# 04_-_MAIN.net
KiCad netlist of a schematic drawn in Altium Designer
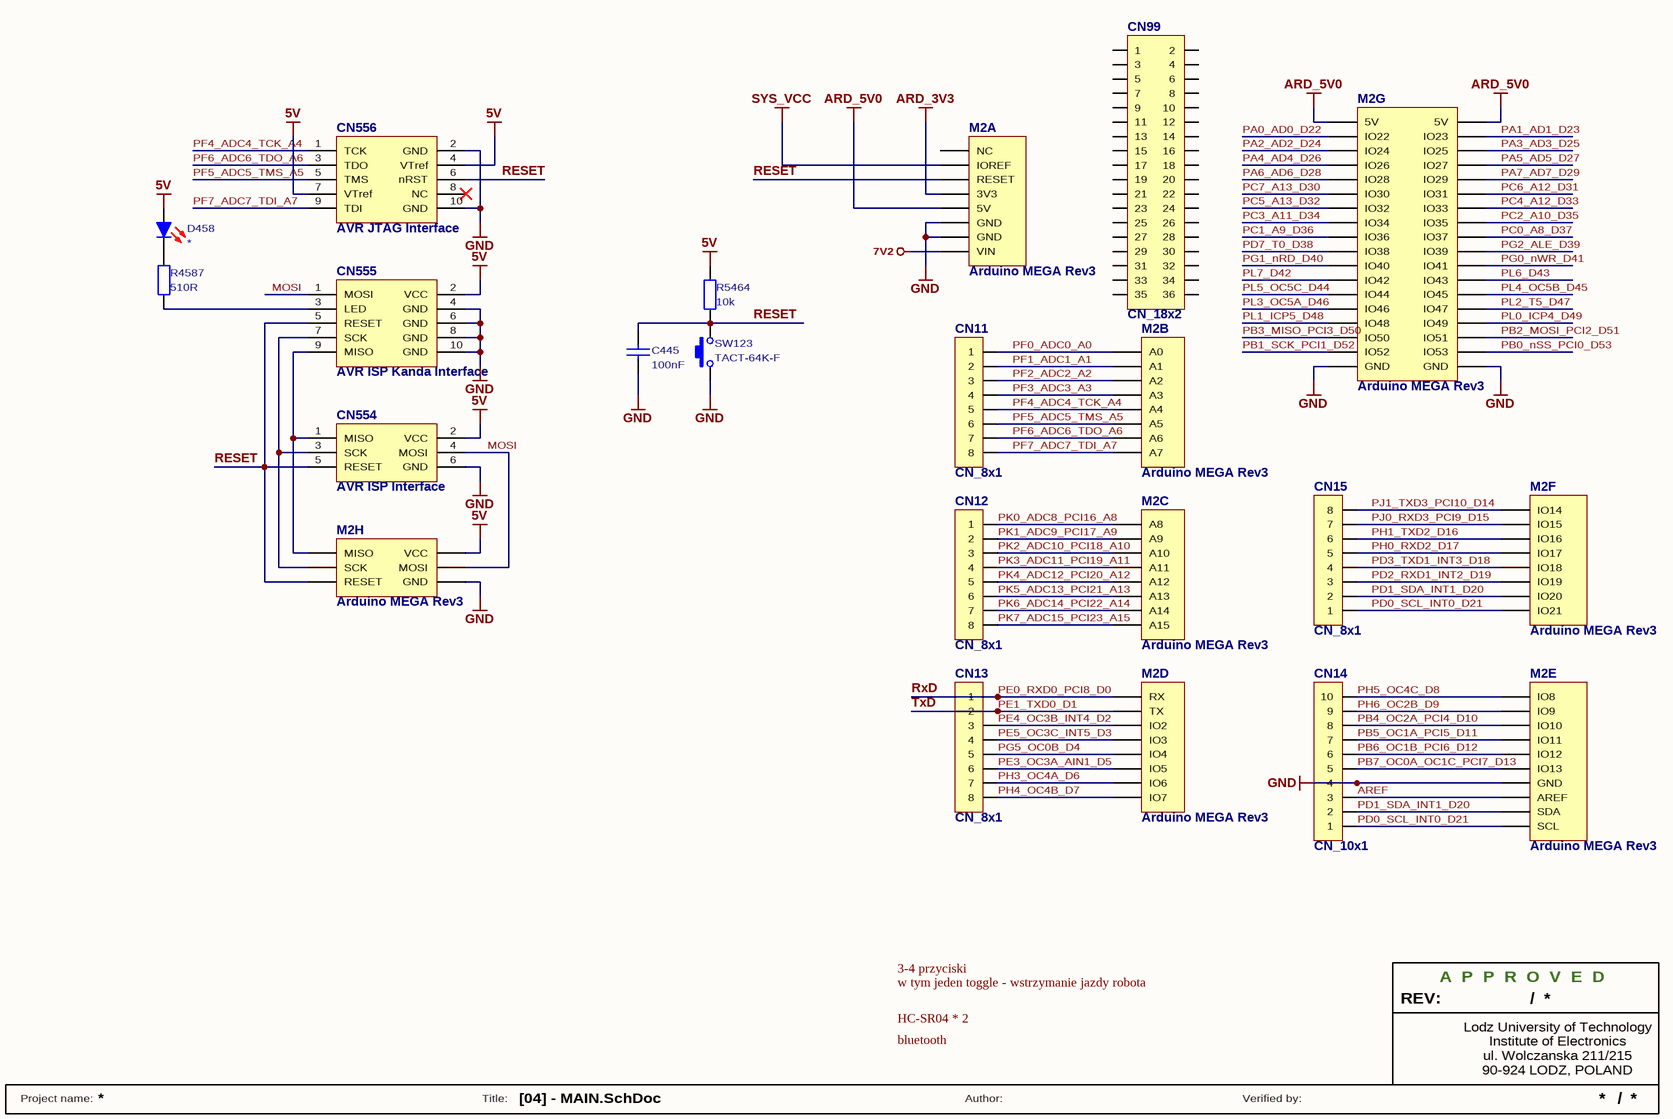
[diagram p0: [04] - MAIN.SchDoc]

(export (version "E")
  (design (tool "Eeschema 10.0.6"))
  (components
    (comp (ref "C445")
      (value "100nF")
      (footprint "C1206")
      (description "Capacitor")
      (libsource (lib "capacitors") (part "Cap"))
    )
    (comp (ref "CN11") (value "CN_8x1") (footprint "GP_8x1") (libsource (lib "") (part "CN_8x1_1")))
    (comp (ref "CN12") (value "CN_8x1") (footprint "GP_8x1") (libsource (lib "") (part "CN_8x1_1")))
    (comp (ref "CN13") (value "CN_8x1") (footprint "GP_8x1") (libsource (lib "") (part "CN_8x1_1")))
    (comp (ref "CN14")
      (value "CN_10x1")
      (footprint "GP_10x1")
      (libsource (lib "goldpin_male") (part "CN_10x1"))
    )
    (comp (ref "CN15") (value "CN_8x1") (footprint "GP_8x1") (libsource (lib "goldpin_male") (part "CN_8x1")))
    (comp (ref "CN99")
      (value "CN_18x2")
      (footprint "GP_18x2")
      (libsource (lib "goldpin_male") (part "CN_18x2"))
    )
    (comp (ref "CN554")
      (value "AVR ISP Interface")
      (footprint "IDC6")
      (description "ISP Programming Header for AVR MCU's")
      (libsource (lib "mcu_prog_and_debug_connectors") (part "AVR ISP Interface"))
    )
    (comp (ref "CN555")
      (value "AVR ISP Kanda Interface")
      (footprint "IDC10")
      (description "Kanda ISP Programming Header for AVR MCU's")
      (libsource (lib "mcu_prog_and_debug_connectors") (part "AVR ISP Kanda Interface"))
    )
    (comp (ref "CN556")
      (value "AVR JTAG Interface")
      (footprint "IDC10")
      (description "JTAG Header for AVR MCU's")
      (libsource (lib "mcu_prog_and_debug_connectors") (part "AVR JTAG Interface"))
    )
    (comp (ref "D458")
      (value "*")
      (footprint "LED1206R")
      (description "RED LED")
      (libsource (lib "leds") (part "LED_RED"))
    )
    (comp (ref "M2")
      (value "Arduino MEGA Rev3")
      (footprint "Arduino_MEGA_UPSIDE_DOWN")
      (description "Arduino MEGA Rev3 Board")
      (libsource (lib "mcu_modules") (part "Arduino MEGA Rev3"))
    )
    (comp (ref "R4587")
      (value "510R")
      (footprint "R1206")
      (description "Resistor")
      (libsource (lib "resistors") (part "Res"))
    )
    (comp (ref "R5464")
      (value "10k")
      (footprint "R1206")
      (description "Resistor")
      (libsource (lib "resistors") (part "Res"))
    )
    (comp (ref "SW123")
      (value "TACT-64K-F")
      (footprint "TACT-64K-F")
      (description "6x6mm THT Tactile SPST-NO Switch")
      (libsource (lib "microswitches") (part "TACT-64K-F"))
    )
  )
  (nets
    (net (code "2") (name "/AREF") (class "Default")
      (node (ref "CN14") (pin "3") (pinfunction "3_3") (pintype "passive"))
      (node (ref "M2") (pin "D15") (pinfunction "AREF_D15") (pintype "passive"))
    )
    (net (code "4") (name "/MOSI") (class "Default")
      (node (ref "CN554") (pin "4") (pinfunction "MOSI_4") (pintype "passive"))
      (node (ref "CN555") (pin "1") (pinfunction "MOSI_1") (pintype "passive"))
      (node (ref "M2") (pin "PROG4") (pinfunction "MOSI_PROG4") (pintype "passive"))
    )
    (net (code "5") (name "/PA0_AD0_D22") (class "Default")
      (node (ref "M2") (pin "D28") (pinfunction "IO22_D28") (pintype "passive"))
    )
    (net (code "6") (name "/PA1_AD1_D23") (class "Default")
      (node (ref "M2") (pin "D29") (pinfunction "IO23_D29") (pintype "passive"))
    )
    (net (code "7") (name "/PA2_AD2_D24") (class "Default")
      (node (ref "M2") (pin "D30") (pinfunction "IO24_D30") (pintype "passive"))
    )
    (net (code "8") (name "/PA3_AD3_D25") (class "Default")
      (node (ref "M2") (pin "D31") (pinfunction "IO25_D31") (pintype "passive"))
    )
    (net (code "9") (name "/PA4_AD4_D26") (class "Default")
      (node (ref "M2") (pin "D32") (pinfunction "IO26_D32") (pintype "passive"))
    )
    (net (code "10") (name "/PA5_AD5_D27") (class "Default")
      (node (ref "M2") (pin "D33") (pinfunction "IO27_D33") (pintype "passive"))
    )
    (net (code "11") (name "/PA6_AD6_D28") (class "Default")
      (node (ref "M2") (pin "D34") (pinfunction "IO28_D34") (pintype "passive"))
    )
    (net (code "12") (name "/PA7_AD7_D29") (class "Default")
      (node (ref "M2") (pin "D35") (pinfunction "IO29_D35") (pintype "passive"))
    )
    (net (code "13") (name "/PB0_nSS_PCI0_D53") (class "Default")
      (node (ref "M2") (pin "D59") (pinfunction "IO53_D59") (pintype "passive"))
    )
    (net (code "14") (name "/PB1_SCK_PCI1_D52") (class "Default")
      (node (ref "M2") (pin "D58") (pinfunction "IO52_D58") (pintype "passive"))
    )
    (net (code "15") (name "/PB2_MOSI_PCI2_D51") (class "Default")
      (node (ref "M2") (pin "D57") (pinfunction "IO51_D57") (pintype "passive"))
    )
    (net (code "16") (name "/PB3_MISO_PCI3_D50") (class "Default")
      (node (ref "M2") (pin "D56") (pinfunction "IO50_D56") (pintype "passive"))
    )
    (net (code "17") (name "/PB4_OC2A_PCI4_D10") (class "Default")
      (node (ref "CN14") (pin "8") (pinfunction "8_8") (pintype "passive"))
      (node (ref "M2") (pin "D10") (pinfunction "IO10_D10") (pintype "passive"))
    )
    (net (code "18") (name "/PB5_OC1A_PCI5_D11") (class "Default")
      (node (ref "CN14") (pin "7") (pinfunction "7_7") (pintype "passive"))
      (node (ref "M2") (pin "D11") (pinfunction "IO11_D11") (pintype "passive"))
    )
    (net (code "19") (name "/PB6_OC1B_PCI6_D12") (class "Default")
      (node (ref "CN14") (pin "6") (pinfunction "6_6") (pintype "passive"))
      (node (ref "M2") (pin "D12") (pinfunction "IO12_D12") (pintype "passive"))
    )
    (net (code "20") (name "/PB7_OC0A_OC1C_PCI7_D13") (class "Default")
      (node (ref "CN14") (pin "5") (pinfunction "5_5") (pintype "passive"))
      (node (ref "M2") (pin "D13") (pinfunction "IO13_D13") (pintype "passive"))
    )
    (net (code "21") (name "/PC0_A8_D37") (class "Default")
      (node (ref "M2") (pin "D43") (pinfunction "IO37_D43") (pintype "passive"))
    )
    (net (code "22") (name "/PC1_A9_D36") (class "Default")
      (node (ref "M2") (pin "D42") (pinfunction "IO36_D42") (pintype "passive"))
    )
    (net (code "23") (name "/PC2_A10_D35") (class "Default")
      (node (ref "M2") (pin "D41") (pinfunction "IO35_D41") (pintype "passive"))
    )
    (net (code "24") (name "/PC3_A11_D34") (class "Default")
      (node (ref "M2") (pin "D40") (pinfunction "IO34_D40") (pintype "passive"))
    )
    (net (code "25") (name "/PC4_A12_D33") (class "Default")
      (node (ref "M2") (pin "D39") (pinfunction "IO33_D39") (pintype "passive"))
    )
    (net (code "26") (name "/PC5_A13_D32") (class "Default")
      (node (ref "M2") (pin "D38") (pinfunction "IO32_D38") (pintype "passive"))
    )
    (net (code "27") (name "/PC6_A12_D31") (class "Default")
      (node (ref "M2") (pin "D37") (pinfunction "IO31_D37") (pintype "passive"))
    )
    (net (code "28") (name "/PC7_A13_D30") (class "Default")
      (node (ref "M2") (pin "D36") (pinfunction "IO30_D36") (pintype "passive"))
    )
    (net (code "29") (name "/PD0_SCL_INT0_D21") (class "Default")
      (node (ref "CN14") (pin "1") (pinfunction "1_1") (pintype "passive"))
      (node (ref "CN15") (pin "1") (pinfunction "1_1") (pintype "passive"))
      (node (ref "M2") (pin "D17") (pinfunction "SCL_D17") (pintype "passive"))
      (node (ref "M2") (pin "D25") (pinfunction "IO21_D25") (pintype "passive"))
    )
    (net (code "30") (name "/PD1_SDA_INT1_D20") (class "Default")
      (node (ref "CN14") (pin "2") (pinfunction "2_2") (pintype "passive"))
      (node (ref "CN15") (pin "2") (pinfunction "2_2") (pintype "passive"))
      (node (ref "M2") (pin "D16") (pinfunction "SDA_D16") (pintype "passive"))
      (node (ref "M2") (pin "D24") (pinfunction "IO20_D24") (pintype "passive"))
    )
    (net (code "31") (name "/PD2_RXD1_INT2_D19") (class "Default")
      (node (ref "CN15") (pin "3") (pinfunction "3_3") (pintype "passive"))
      (node (ref "M2") (pin "D23") (pinfunction "IO19_D23") (pintype "passive"))
    )
    (net (code "32") (name "/PD3_TXD1_INT3_D18") (class "Default")
      (node (ref "CN15") (pin "4") (pinfunction "4_4") (pintype "passive"))
      (node (ref "M2") (pin "D22") (pinfunction "IO18_D22") (pintype "passive"))
    )
    (net (code "33") (name "/PD7_T0_D38") (class "Default")
      (node (ref "M2") (pin "D44") (pinfunction "IO38_D44") (pintype "passive"))
    )
    (net (code "34") (name "/PE0_RXD0_PCI8_D0") (class "Default")
      (node (ref "CN13") (pin "1") (pinfunction "1_1") (pintype "passive"))
      (node (ref "M2") (pin "D0") (pinfunction "RX_D0") (pintype "passive"))
    )
    (net (code "35") (name "/PE1_TXD0_D1") (class "Default")
      (node (ref "CN13") (pin "2") (pinfunction "2_2") (pintype "passive"))
      (node (ref "M2") (pin "D1") (pinfunction "TX_D1") (pintype "passive"))
    )
    (net (code "36") (name "/PE3_OC3A_AIN1_D5") (class "Default")
      (node (ref "CN13") (pin "6") (pinfunction "6_6") (pintype "passive"))
      (node (ref "M2") (pin "D5") (pinfunction "IO5_D5") (pintype "passive"))
    )
    (net (code "37") (name "/PE4_OC3B_INT4_D2") (class "Default")
      (node (ref "CN13") (pin "3") (pinfunction "3_3") (pintype "passive"))
      (node (ref "M2") (pin "D2") (pinfunction "IO2_D2") (pintype "passive"))
    )
    (net (code "38") (name "/PE5_OC3C_INT5_D3") (class "Default")
      (node (ref "CN13") (pin "4") (pinfunction "4_4") (pintype "passive"))
      (node (ref "M2") (pin "D3") (pinfunction "IO3_D3") (pintype "passive"))
    )
    (net (code "39") (name "/PF0_ADC0_A0") (class "Default")
      (node (ref "CN11") (pin "1") (pinfunction "1_1") (pintype "passive"))
      (node (ref "M2") (pin "A0") (pinfunction "A0_A0") (pintype "passive"))
    )
    (net (code "40") (name "/PF1_ADC1_A1") (class "Default")
      (node (ref "CN11") (pin "2") (pinfunction "2_2") (pintype "passive"))
      (node (ref "M2") (pin "A1") (pinfunction "A1_A1") (pintype "passive"))
    )
    (net (code "41") (name "/PF2_ADC2_A2") (class "Default")
      (node (ref "CN11") (pin "3") (pinfunction "3_3") (pintype "passive"))
      (node (ref "M2") (pin "A2") (pinfunction "A2_A2") (pintype "passive"))
    )
    (net (code "42") (name "/PF3_ADC3_A3") (class "Default")
      (node (ref "CN11") (pin "4") (pinfunction "4_4") (pintype "passive"))
      (node (ref "M2") (pin "A3") (pinfunction "A3_A3") (pintype "passive"))
    )
    (net (code "43") (name "/PF4_ADC4_TCK_A4") (class "Default")
      (node (ref "CN11") (pin "5") (pinfunction "5_5") (pintype "passive"))
      (node (ref "CN556") (pin "1") (pinfunction "TCK_1") (pintype "passive"))
      (node (ref "M2") (pin "A4") (pinfunction "A4_A4") (pintype "passive"))
    )
    (net (code "44") (name "/PF5_ADC5_TMS_A5") (class "Default")
      (node (ref "CN11") (pin "6") (pinfunction "6_6") (pintype "passive"))
      (node (ref "CN556") (pin "5") (pinfunction "TMS_5") (pintype "passive"))
      (node (ref "M2") (pin "A5") (pinfunction "A5_A5") (pintype "passive"))
    )
    (net (code "45") (name "/PF6_ADC6_TDO_A6") (class "Default")
      (node (ref "CN11") (pin "7") (pinfunction "7_7") (pintype "passive"))
      (node (ref "CN556") (pin "3") (pinfunction "TDO_3") (pintype "passive"))
      (node (ref "M2") (pin "A6") (pinfunction "A6_A6") (pintype "passive"))
    )
    (net (code "46") (name "/PF7_ADC7_TDI_A7") (class "Default")
      (node (ref "CN11") (pin "8") (pinfunction "8_8") (pintype "passive"))
      (node (ref "CN556") (pin "9") (pinfunction "TDI_9") (pintype "passive"))
      (node (ref "M2") (pin "A7") (pinfunction "A7_A7") (pintype "passive"))
    )
    (net (code "47") (name "/PG0_nWR_D41") (class "Default")
      (node (ref "M2") (pin "D47") (pinfunction "IO41_D47") (pintype "passive"))
    )
    (net (code "48") (name "/PG1_nRD_D40") (class "Default")
      (node (ref "M2") (pin "D46") (pinfunction "IO40_D46") (pintype "passive"))
    )
    (net (code "49") (name "/PG2_ALE_D39") (class "Default")
      (node (ref "M2") (pin "D45") (pinfunction "IO39_D45") (pintype "passive"))
    )
    (net (code "50") (name "/PG5_OC0B_D4") (class "Default")
      (node (ref "CN13") (pin "5") (pinfunction "5_5") (pintype "passive"))
      (node (ref "M2") (pin "D4") (pinfunction "IO4_D4") (pintype "passive"))
    )
    (net (code "51") (name "/PH0_RXD2_D17") (class "Default")
      (node (ref "CN15") (pin "5") (pinfunction "5_5") (pintype "passive"))
      (node (ref "M2") (pin "D21") (pinfunction "IO17_D21") (pintype "passive"))
    )
    (net (code "52") (name "/PH1_TXD2_D16") (class "Default")
      (node (ref "CN15") (pin "6") (pinfunction "6_6") (pintype "passive"))
      (node (ref "M2") (pin "D20") (pinfunction "IO16_D20") (pintype "passive"))
    )
    (net (code "53") (name "/PH3_OC4A_D6") (class "Default")
      (node (ref "CN13") (pin "7") (pinfunction "7_7") (pintype "passive"))
      (node (ref "M2") (pin "D6") (pinfunction "IO6_D6") (pintype "passive"))
    )
    (net (code "54") (name "/PH4_OC4B_D7") (class "Default")
      (node (ref "CN13") (pin "8") (pinfunction "8_8") (pintype "passive"))
      (node (ref "M2") (pin "D7") (pinfunction "IO7_D7") (pintype "passive"))
    )
    (net (code "55") (name "/PH5_OC4C_D8") (class "Default")
      (node (ref "CN14") (pin "10") (pinfunction "10_10") (pintype "passive"))
      (node (ref "M2") (pin "D8") (pinfunction "IO8_D8") (pintype "passive"))
    )
    (net (code "56") (name "/PH6_OC2B_D9") (class "Default")
      (node (ref "CN14") (pin "9") (pinfunction "9_9") (pintype "passive"))
      (node (ref "M2") (pin "D9") (pinfunction "IO9_D9") (pintype "passive"))
    )
    (net (code "57") (name "/PJ0_RXD3_PCI9_D15") (class "Default")
      (node (ref "CN15") (pin "7") (pinfunction "7_7") (pintype "passive"))
      (node (ref "M2") (pin "D19") (pinfunction "IO15_D19") (pintype "passive"))
    )
    (net (code "58") (name "/PJ1_TXD3_PCI10_D14") (class "Default")
      (node (ref "CN15") (pin "8") (pinfunction "8_8") (pintype "passive"))
      (node (ref "M2") (pin "D18") (pinfunction "IO14_D18") (pintype "passive"))
    )
    (net (code "59") (name "/PK0_ADC8_PCI16_A8") (class "Default")
      (node (ref "CN12") (pin "1") (pinfunction "1_1") (pintype "passive"))
      (node (ref "M2") (pin "A8") (pinfunction "A8_A8") (pintype "passive"))
    )
    (net (code "60") (name "/PK1_ADC9_PCI17_A9") (class "Default")
      (node (ref "CN12") (pin "2") (pinfunction "2_2") (pintype "passive"))
      (node (ref "M2") (pin "A9") (pinfunction "A9_A9") (pintype "passive"))
    )
    (net (code "61") (name "/PK2_ADC10_PCI18_A10") (class "Default")
      (node (ref "CN12") (pin "3") (pinfunction "3_3") (pintype "passive"))
      (node (ref "M2") (pin "A10") (pinfunction "A10_A10") (pintype "passive"))
    )
    (net (code "62") (name "/PK3_ADC11_PCI19_A11") (class "Default")
      (node (ref "CN12") (pin "4") (pinfunction "4_4") (pintype "passive"))
      (node (ref "M2") (pin "A11") (pinfunction "A11_A11") (pintype "passive"))
    )
    (net (code "63") (name "/PK4_ADC12_PCI20_A12") (class "Default")
      (node (ref "CN12") (pin "5") (pinfunction "5_5") (pintype "passive"))
      (node (ref "M2") (pin "A12") (pinfunction "A12_A12") (pintype "passive"))
    )
    (net (code "64") (name "/PK5_ADC13_PCI21_A13") (class "Default")
      (node (ref "CN12") (pin "6") (pinfunction "6_6") (pintype "passive"))
      (node (ref "M2") (pin "A13") (pinfunction "A13_A13") (pintype "passive"))
    )
    (net (code "65") (name "/PK6_ADC14_PCI22_A14") (class "Default")
      (node (ref "CN12") (pin "7") (pinfunction "7_7") (pintype "passive"))
      (node (ref "M2") (pin "A14") (pinfunction "A14_A14") (pintype "passive"))
    )
    (net (code "66") (name "/PK7_ADC15_PCI23_A15") (class "Default")
      (node (ref "CN12") (pin "8") (pinfunction "8_8") (pintype "passive"))
      (node (ref "M2") (pin "A15") (pinfunction "A15_A15") (pintype "passive"))
    )
    (net (code "67") (name "/PL0_ICP4_D49") (class "Default")
      (node (ref "M2") (pin "D55") (pinfunction "IO49_D55") (pintype "passive"))
    )
    (net (code "68") (name "/PL1_ICP5_D48") (class "Default")
      (node (ref "M2") (pin "D54") (pinfunction "IO48_D54") (pintype "passive"))
    )
    (net (code "69") (name "/PL2_T5_D47") (class "Default")
      (node (ref "M2") (pin "D53") (pinfunction "IO47_D53") (pintype "passive"))
    )
    (net (code "70") (name "/PL3_OC5A_D46") (class "Default")
      (node (ref "M2") (pin "D52") (pinfunction "IO46_D52") (pintype "passive"))
    )
    (net (code "71") (name "/PL4_OC5B_D45") (class "Default")
      (node (ref "M2") (pin "D51") (pinfunction "IO45_D51") (pintype "passive"))
    )
    (net (code "72") (name "/PL5_OC5C_D44") (class "Default")
      (node (ref "M2") (pin "D50") (pinfunction "IO44_D50") (pintype "passive"))
    )
    (net (code "73") (name "/PL6_D43") (class "Default")
      (node (ref "M2") (pin "D49") (pinfunction "IO43_D49") (pintype "passive"))
    )
    (net (code "74") (name "/PL7_D42") (class "Default")
      (node (ref "M2") (pin "D48") (pinfunction "IO42_D48") (pintype "passive"))
    )
    (net (code "75") (name "/RESET") (class "Default")
      (node (ref "C445") (pin "2") (pinfunction "2_2") (pintype "passive"))
      (node (ref "CN554") (pin "5") (pinfunction "RESET_5") (pintype "passive"))
      (node (ref "CN555") (pin "5") (pinfunction "RESET_5") (pintype "passive"))
      (node (ref "CN556") (pin "6") (pinfunction "nRST_6") (pintype "passive"))
      (node (ref "M2") (pin "P3") (pinfunction "RESET_P3") (pintype "passive"))
      (node (ref "M2") (pin "PROG5") (pinfunction "RESET_PROG5") (pintype "passive"))
      (node (ref "R5464") (pin "1") (pinfunction "1_1") (pintype "passive"))
      (node (ref "SW123") (pin "2") (pinfunction "2_2") (pintype "passive"))
    )
    (net (code "78") (name "5V") (class "Default")
      (node (ref "CN554") (pin "2") (pinfunction "VCC_2") (pintype "passive"))
      (node (ref "CN555") (pin "2") (pinfunction "VCC_2") (pintype "passive"))
      (node (ref "CN556") (pin "4") (pinfunction "VTref_4") (pintype "passive"))
      (node (ref "CN556") (pin "7") (pinfunction "VTref_7") (pintype "passive"))
      (node (ref "D458") (pin "1") (pinfunction "A_1") (pintype "passive"))
      (node (ref "M2") (pin "PROG2") (pinfunction "VCC_PROG2") (pintype "passive"))
      (node (ref "R5464") (pin "2") (pinfunction "2_2") (pintype "passive"))
    )
    (net (code "79") (name "7V2") (class "Default")
      (node (ref "M2") (pin "P8") (pinfunction "VIN_P8") (pintype "passive"))
    )
    (net (code "80") (name "ARD_3V3") (class "Default")
      (node (ref "M2") (pin "P4") (pinfunction "3V3_P4") (pintype "passive"))
    )
    (net (code "81") (name "ARD_5V0") (class "Default")
      (node (ref "M2") (pin "D26") (pinfunction "5V_D26") (pintype "passive"))
      (node (ref "M2") (pin "D27") (pinfunction "5V_D27") (pintype "passive"))
      (node (ref "M2") (pin "P5") (pinfunction "5V_P5") (pintype "passive"))
    )
    (net (code "82") (name "GND") (class "Default")
      (node (ref "C445") (pin "1") (pinfunction "1_1") (pintype "passive"))
      (node (ref "CN14") (pin "4") (pinfunction "4_4") (pintype "passive"))
      (node (ref "CN554") (pin "6") (pinfunction "GND_6") (pintype "passive"))
      (node (ref "CN555") (pin "10") (pinfunction "GND_10") (pintype "passive"))
      (node (ref "CN555") (pin "4") (pinfunction "GND_4") (pintype "passive"))
      (node (ref "CN555") (pin "6") (pinfunction "GND_6") (pintype "passive"))
      (node (ref "CN555") (pin "8") (pinfunction "GND_8") (pintype "passive"))
      (node (ref "CN556") (pin "10") (pinfunction "GND_10") (pintype "passive"))
      (node (ref "CN556") (pin "2") (pinfunction "GND_2") (pintype "passive"))
      (node (ref "M2") (pin "D14") (pinfunction "GND_D14") (pintype "passive"))
      (node (ref "M2") (pin "D60") (pinfunction "GND_D60") (pintype "passive"))
      (node (ref "M2") (pin "D61") (pinfunction "GND_D61") (pintype "passive"))
      (node (ref "M2") (pin "P6") (pinfunction "GND_P6") (pintype "passive"))
      (node (ref "M2") (pin "P7") (pinfunction "GND_P7") (pintype "passive"))
      (node (ref "M2") (pin "PROG6") (pinfunction "GND_PROG6") (pintype "passive"))
      (node (ref "SW123") (pin "1") (pinfunction "1_1") (pintype "passive"))
    )
    (net (code "83") (name "Net-(CN554-MISO)") (class "Default")
      (node (ref "CN554") (pin "1") (pinfunction "MISO_1") (pintype "passive"))
      (node (ref "CN555") (pin "9") (pinfunction "MISO_9") (pintype "passive"))
      (node (ref "M2") (pin "PROG1") (pinfunction "MISO_PROG1") (pintype "passive"))
    )
    (net (code "84") (name "Net-(CN554-SCK)") (class "Default")
      (node (ref "CN554") (pin "3") (pinfunction "SCK_3") (pintype "passive"))
      (node (ref "CN555") (pin "7") (pinfunction "SCK_7") (pintype "passive"))
      (node (ref "M2") (pin "PROG3") (pinfunction "SCK_PROG3") (pintype "passive"))
    )
    (net (code "85") (name "Net-(CN555-LED)") (class "Default")
      (node (ref "CN555") (pin "3") (pinfunction "LED_3") (pintype "passive"))
      (node (ref "R4587") (pin "1") (pinfunction "1_1") (pintype "passive"))
    )
    (net (code "86") (name "Net-(D458-K)") (class "Default")
      (node (ref "D458") (pin "2") (pinfunction "K_2") (pintype "passive"))
      (node (ref "R4587") (pin "2") (pinfunction "2_2") (pintype "passive"))
    )
    (net (code "87") (name "SYS_VCC") (class "Default")
      (node (ref "M2") (pin "P2") (pinfunction "IOREF_P2") (pintype "passive"))
    )
    (net (code "88") (name "unconnected-(CN99-Pad1)") (class "Default")
      (node (ref "CN99") (pin "1") (pinfunction "1_1") (pintype "passive"))
    )
    (net (code "89") (name "unconnected-(CN99-Pad2)") (class "Default")
      (node (ref "CN99") (pin "2") (pinfunction "2_2") (pintype "passive"))
    )
    (net (code "90") (name "unconnected-(CN99-Pad3)") (class "Default")
      (node (ref "CN99") (pin "3") (pinfunction "3_3") (pintype "passive"))
    )
    (net (code "91") (name "unconnected-(CN99-Pad4)") (class "Default")
      (node (ref "CN99") (pin "4") (pinfunction "4_4") (pintype "passive"))
    )
    (net (code "92") (name "unconnected-(CN99-Pad5)") (class "Default")
      (node (ref "CN99") (pin "5") (pinfunction "5_5") (pintype "passive"))
    )
    (net (code "93") (name "unconnected-(CN99-Pad6)") (class "Default")
      (node (ref "CN99") (pin "6") (pinfunction "6_6") (pintype "passive"))
    )
    (net (code "94") (name "unconnected-(CN99-Pad7)") (class "Default")
      (node (ref "CN99") (pin "7") (pinfunction "7_7") (pintype "passive"))
    )
    (net (code "95") (name "unconnected-(CN99-Pad8)") (class "Default")
      (node (ref "CN99") (pin "8") (pinfunction "8_8") (pintype "passive"))
    )
    (net (code "96") (name "unconnected-(CN99-Pad9)") (class "Default")
      (node (ref "CN99") (pin "9") (pinfunction "9_9") (pintype "passive"))
    )
    (net (code "97") (name "unconnected-(CN99-Pad10)") (class "Default")
      (node (ref "CN99") (pin "10") (pinfunction "10_10") (pintype "passive"))
    )
    (net (code "98") (name "unconnected-(CN99-Pad11)") (class "Default")
      (node (ref "CN99") (pin "11") (pinfunction "11_11") (pintype "passive"))
    )
    (net (code "99") (name "unconnected-(CN99-Pad12)") (class "Default")
      (node (ref "CN99") (pin "12") (pinfunction "12_12") (pintype "passive"))
    )
    (net (code "100") (name "unconnected-(CN99-Pad13)") (class "Default")
      (node (ref "CN99") (pin "13") (pinfunction "13_13") (pintype "passive"))
    )
    (net (code "101") (name "unconnected-(CN99-Pad14)") (class "Default")
      (node (ref "CN99") (pin "14") (pinfunction "14_14") (pintype "passive"))
    )
    (net (code "102") (name "unconnected-(CN99-Pad15)") (class "Default")
      (node (ref "CN99") (pin "15") (pinfunction "15_15") (pintype "passive"))
    )
    (net (code "103") (name "unconnected-(CN99-Pad16)") (class "Default")
      (node (ref "CN99") (pin "16") (pinfunction "16_16") (pintype "passive"))
    )
    (net (code "104") (name "unconnected-(CN99-Pad17)") (class "Default")
      (node (ref "CN99") (pin "17") (pinfunction "17_17") (pintype "passive"))
    )
    (net (code "105") (name "unconnected-(CN99-Pad18)") (class "Default")
      (node (ref "CN99") (pin "18") (pinfunction "18_18") (pintype "passive"))
    )
    (net (code "106") (name "unconnected-(CN99-Pad19)") (class "Default")
      (node (ref "CN99") (pin "19") (pinfunction "19_19") (pintype "passive"))
    )
    (net (code "107") (name "unconnected-(CN99-Pad20)") (class "Default")
      (node (ref "CN99") (pin "20") (pinfunction "20_20") (pintype "passive"))
    )
    (net (code "108") (name "unconnected-(CN99-Pad21)") (class "Default")
      (node (ref "CN99") (pin "21") (pinfunction "21_21") (pintype "passive"))
    )
    (net (code "109") (name "unconnected-(CN99-Pad22)") (class "Default")
      (node (ref "CN99") (pin "22") (pinfunction "22_22") (pintype "passive"))
    )
    (net (code "110") (name "unconnected-(CN99-Pad23)") (class "Default")
      (node (ref "CN99") (pin "23") (pinfunction "23_23") (pintype "passive"))
    )
    (net (code "111") (name "unconnected-(CN99-Pad24)") (class "Default")
      (node (ref "CN99") (pin "24") (pinfunction "24_24") (pintype "passive"))
    )
    (net (code "112") (name "unconnected-(CN99-Pad25)") (class "Default")
      (node (ref "CN99") (pin "25") (pinfunction "25_25") (pintype "passive"))
    )
    (net (code "113") (name "unconnected-(CN99-Pad26)") (class "Default")
      (node (ref "CN99") (pin "26") (pinfunction "26_26") (pintype "passive"))
    )
    (net (code "114") (name "unconnected-(CN99-Pad27)") (class "Default")
      (node (ref "CN99") (pin "27") (pinfunction "27_27") (pintype "passive"))
    )
    (net (code "115") (name "unconnected-(CN99-Pad28)") (class "Default")
      (node (ref "CN99") (pin "28") (pinfunction "28_28") (pintype "passive"))
    )
    (net (code "116") (name "unconnected-(CN99-Pad29)") (class "Default")
      (node (ref "CN99") (pin "29") (pinfunction "29_29") (pintype "passive"))
    )
    (net (code "117") (name "unconnected-(CN99-Pad30)") (class "Default")
      (node (ref "CN99") (pin "30") (pinfunction "30_30") (pintype "passive"))
    )
    (net (code "118") (name "unconnected-(CN99-Pad31)") (class "Default")
      (node (ref "CN99") (pin "31") (pinfunction "31_31") (pintype "passive"))
    )
    (net (code "119") (name "unconnected-(CN99-Pad32)") (class "Default")
      (node (ref "CN99") (pin "32") (pinfunction "32_32") (pintype "passive"))
    )
    (net (code "120") (name "unconnected-(CN99-Pad33)") (class "Default")
      (node (ref "CN99") (pin "33") (pinfunction "33_33") (pintype "passive"))
    )
    (net (code "121") (name "unconnected-(CN99-Pad34)") (class "Default")
      (node (ref "CN99") (pin "34") (pinfunction "34_34") (pintype "passive"))
    )
    (net (code "122") (name "unconnected-(CN99-Pad35)") (class "Default")
      (node (ref "CN99") (pin "35") (pinfunction "35_35") (pintype "passive"))
    )
    (net (code "123") (name "unconnected-(CN99-Pad36)") (class "Default")
      (node (ref "CN99") (pin "36") (pinfunction "36_36") (pintype "passive"))
    )
    (net (code "124") (name "unconnected-(CN556-NC-Pad8)") (class "Default")
      (node (ref "CN556") (pin "8") (pinfunction "NC_8") (pintype "passive+no_connect"))
    )
    (net (code "125") (name "unconnected-(M2A-NC-PadP1)") (class "Default")
      (node (ref "M2") (pin "P1") (pinfunction "NC_P1") (pintype "passive"))
    )
  )
)
